# Interfaces.net
KiCad netlist of a schematic drawn in Altium Designer
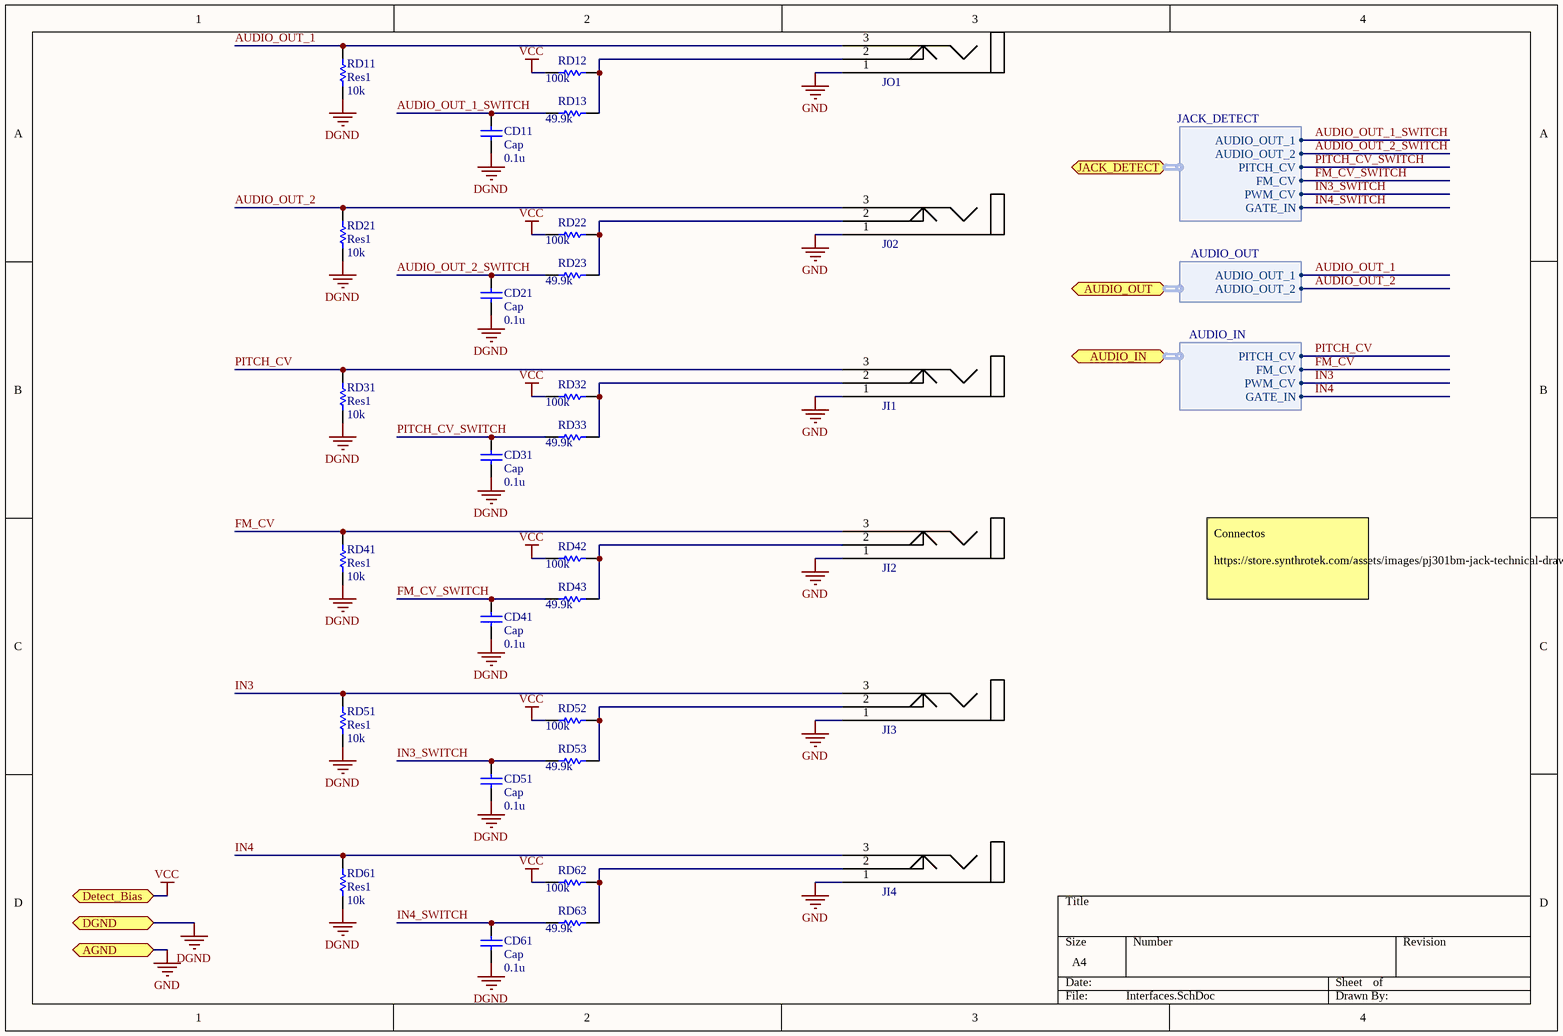
[diagram p0: Interfaces.SchDoc]

(export (version "E")
  (design (tool "Eeschema 10.0.6"))
  (components
    (comp (ref "CD11")
      (value "Cap")
      (footprint "C 0603 / 1608")
      (description "Capacitor")
      (fields (field (name "ALTIUM_VALUE") "0.1u") (field (name "PUBLISHER") "Altium Limited"))
      (libsource (lib "Standard") (part "Cap"))
    )
    (comp (ref "CD21")
      (value "Cap")
      (footprint "C 0603 / 1608")
      (description "Capacitor")
      (fields (field (name "ALTIUM_VALUE") "0.1u") (field (name "PUBLISHER") "Altium Limited"))
      (libsource (lib "Standard") (part "Cap"))
    )
    (comp (ref "CD31")
      (value "Cap")
      (footprint "C 0603 / 1608")
      (description "Capacitor")
      (fields (field (name "ALTIUM_VALUE") "0.1u") (field (name "PUBLISHER") "Altium Limited"))
      (libsource (lib "Standard") (part "Cap"))
    )
    (comp (ref "CD41")
      (value "Cap")
      (footprint "C 0603 / 1608")
      (description "Capacitor")
      (fields (field (name "ALTIUM_VALUE") "0.1u") (field (name "PUBLISHER") "Altium Limited"))
      (libsource (lib "Standard") (part "Cap"))
    )
    (comp (ref "CD51")
      (value "Cap")
      (footprint "C 0603 / 1608")
      (description "Capacitor")
      (fields (field (name "ALTIUM_VALUE") "0.1u") (field (name "PUBLISHER") "Altium Limited"))
      (libsource (lib "Standard") (part "Cap"))
    )
    (comp (ref "CD61")
      (value "Cap")
      (footprint "C 0603 / 1608")
      (description "Capacitor")
      (fields (field (name "ALTIUM_VALUE") "0.1u") (field (name "PUBLISHER") "Altium Limited"))
      (libsource (lib "Standard") (part "Cap"))
    )
    (comp (ref "J02") (value "PJ-301") (footprint "PJ-301") (libsource (lib "Connectors") (part "PJ-301")))
    (comp (ref "JI1") (value "PJ-301") (footprint "PJ-301") (libsource (lib "Connectors") (part "PJ-301")))
    (comp (ref "JI2") (value "PJ-301") (footprint "PJ-301") (libsource (lib "Connectors") (part "PJ-301")))
    (comp (ref "JI3") (value "PJ-301") (footprint "PJ-301") (libsource (lib "Connectors") (part "PJ-301")))
    (comp (ref "JI4") (value "PJ-301") (footprint "PJ-301") (libsource (lib "Connectors") (part "PJ-301")))
    (comp (ref "JO1") (value "PJ-301") (footprint "PJ-301") (libsource (lib "Connectors") (part "PJ-301")))
    (comp (ref "RD11")
      (value "Res1")
      (footprint "RES0603R")
      (description "Resistor")
      (fields (field (name "ALTIUM_VALUE") "10k") (field (name "PUBLISHER") "Altium Limited"))
      (libsource (lib "Standard") (part "Res1"))
    )
    (comp (ref "RD12")
      (value "100k")
      (footprint "RES0603R")
      (description "Resistor")
      (fields (field (name "Comment") "Res1") (field (name "PUBLISHER") "Altium Limited"))
      (libsource (lib "Standard") (part "Res1"))
    )
    (comp (ref "RD13")
      (value "49.9k")
      (footprint "RES0603R")
      (description "Resistor")
      (fields (field (name "Comment") "Res1") (field (name "PUBLISHER") "Altium Limited"))
      (libsource (lib "Standard") (part "Res1"))
    )
    (comp (ref "RD21")
      (value "Res1")
      (footprint "RES0603R")
      (description "Resistor")
      (fields (field (name "ALTIUM_VALUE") "10k") (field (name "PUBLISHER") "Altium Limited"))
      (libsource (lib "Standard") (part "Res1"))
    )
    (comp (ref "RD22")
      (value "100k")
      (footprint "RES0603R")
      (description "Resistor")
      (fields (field (name "Comment") "Res1") (field (name "PUBLISHER") "Altium Limited"))
      (libsource (lib "Standard") (part "Res1"))
    )
    (comp (ref "RD23")
      (value "49.9k")
      (footprint "RES0603R")
      (description "Resistor")
      (fields (field (name "Comment") "Res1") (field (name "PUBLISHER") "Altium Limited"))
      (libsource (lib "Standard") (part "Res1"))
    )
    (comp (ref "RD31")
      (value "Res1")
      (footprint "RES0603R")
      (description "Resistor")
      (fields (field (name "ALTIUM_VALUE") "10k") (field (name "PUBLISHER") "Altium Limited"))
      (libsource (lib "Standard") (part "Res1"))
    )
    (comp (ref "RD32")
      (value "100k")
      (footprint "RES0603R")
      (description "Resistor")
      (fields (field (name "Comment") "Res1") (field (name "PUBLISHER") "Altium Limited"))
      (libsource (lib "Standard") (part "Res1"))
    )
    (comp (ref "RD33")
      (value "49.9k")
      (footprint "RES0603R")
      (description "Resistor")
      (fields (field (name "Comment") "Res1") (field (name "PUBLISHER") "Altium Limited"))
      (libsource (lib "Standard") (part "Res1"))
    )
    (comp (ref "RD41")
      (value "Res1")
      (footprint "RES0603R")
      (description "Resistor")
      (fields (field (name "ALTIUM_VALUE") "10k") (field (name "PUBLISHER") "Altium Limited"))
      (libsource (lib "Standard") (part "Res1"))
    )
    (comp (ref "RD42")
      (value "100k")
      (footprint "RES0603R")
      (description "Resistor")
      (fields (field (name "Comment") "Res1") (field (name "PUBLISHER") "Altium Limited"))
      (libsource (lib "Standard") (part "Res1"))
    )
    (comp (ref "RD43")
      (value "49.9k")
      (footprint "RES0603R")
      (description "Resistor")
      (fields (field (name "Comment") "Res1") (field (name "PUBLISHER") "Altium Limited"))
      (libsource (lib "Standard") (part "Res1"))
    )
    (comp (ref "RD51")
      (value "Res1")
      (footprint "RES0603R")
      (description "Resistor")
      (fields (field (name "ALTIUM_VALUE") "10k") (field (name "PUBLISHER") "Altium Limited"))
      (libsource (lib "Standard") (part "Res1"))
    )
    (comp (ref "RD52")
      (value "100k")
      (footprint "RES0603R")
      (description "Resistor")
      (fields (field (name "Comment") "Res1") (field (name "PUBLISHER") "Altium Limited"))
      (libsource (lib "Standard") (part "Res1"))
    )
    (comp (ref "RD53")
      (value "49.9k")
      (footprint "RES0603R")
      (description "Resistor")
      (fields (field (name "Comment") "Res1") (field (name "PUBLISHER") "Altium Limited"))
      (libsource (lib "Standard") (part "Res1"))
    )
    (comp (ref "RD61")
      (value "Res1")
      (footprint "RES0603R")
      (description "Resistor")
      (fields (field (name "ALTIUM_VALUE") "10k") (field (name "PUBLISHER") "Altium Limited"))
      (libsource (lib "Standard") (part "Res1"))
    )
    (comp (ref "RD62")
      (value "100k")
      (footprint "RES0603R")
      (description "Resistor")
      (fields (field (name "Comment") "Res1") (field (name "PUBLISHER") "Altium Limited"))
      (libsource (lib "Standard") (part "Res1"))
    )
    (comp (ref "RD63")
      (value "49.9k")
      (footprint "RES0603R")
      (description "Resistor")
      (fields (field (name "Comment") "Res1") (field (name "PUBLISHER") "Altium Limited"))
      (libsource (lib "Standard") (part "Res1"))
    )
  )
  (nets
    (net (code "4") (name "/AUDIO_OUT_1") (class "Default")
      (node (ref "JO1") (pin "3") (pinfunction "Ring_3") (pintype "passive"))
      (node (ref "RD11") (pin "2") (pinfunction "2_2") (pintype "passive"))
    )
    (net (code "5") (name "/AUDIO_OUT_1_SWITCH") (class "Default")
      (node (ref "CD11") (pin "2") (pinfunction "2_2") (pintype "passive"))
      (node (ref "RD13") (pin "2") (pinfunction "2_2") (pintype "passive"))
    )
    (net (code "6") (name "/AUDIO_OUT_2") (class "Default")
      (node (ref "J02") (pin "3") (pinfunction "Ring_3") (pintype "passive"))
      (node (ref "RD21") (pin "2") (pinfunction "2_2") (pintype "passive"))
    )
    (net (code "7") (name "/AUDIO_OUT_2_SWITCH") (class "Default")
      (node (ref "CD21") (pin "2") (pinfunction "2_2") (pintype "passive"))
      (node (ref "RD23") (pin "2") (pinfunction "2_2") (pintype "passive"))
    )
    (net (code "8") (name "/FM_CV") (class "Default")
      (node (ref "JI2") (pin "3") (pinfunction "Ring_3") (pintype "passive"))
      (node (ref "RD41") (pin "2") (pinfunction "2_2") (pintype "passive"))
    )
    (net (code "9") (name "/FM_CV_SWITCH") (class "Default")
      (node (ref "CD41") (pin "2") (pinfunction "2_2") (pintype "passive"))
      (node (ref "RD43") (pin "2") (pinfunction "2_2") (pintype "passive"))
    )
    (net (code "10") (name "/IN3") (class "Default")
      (node (ref "JI3") (pin "3") (pinfunction "Ring_3") (pintype "passive"))
      (node (ref "RD51") (pin "2") (pinfunction "2_2") (pintype "passive"))
    )
    (net (code "11") (name "/IN3_SWITCH") (class "Default")
      (node (ref "CD51") (pin "2") (pinfunction "2_2") (pintype "passive"))
      (node (ref "RD53") (pin "2") (pinfunction "2_2") (pintype "passive"))
    )
    (net (code "12") (name "/IN4") (class "Default")
      (node (ref "JI4") (pin "3") (pinfunction "Ring_3") (pintype "passive"))
      (node (ref "RD61") (pin "2") (pinfunction "2_2") (pintype "passive"))
    )
    (net (code "13") (name "/IN4_SWITCH") (class "Default")
      (node (ref "CD61") (pin "2") (pinfunction "2_2") (pintype "passive"))
      (node (ref "RD63") (pin "2") (pinfunction "2_2") (pintype "passive"))
    )
    (net (code "14") (name "/PITCH_CV") (class "Default")
      (node (ref "JI1") (pin "3") (pinfunction "Ring_3") (pintype "passive"))
      (node (ref "RD31") (pin "2") (pinfunction "2_2") (pintype "passive"))
    )
    (net (code "15") (name "/PITCH_CV_SWITCH") (class "Default")
      (node (ref "CD31") (pin "2") (pinfunction "2_2") (pintype "passive"))
      (node (ref "RD33") (pin "2") (pinfunction "2_2") (pintype "passive"))
    )
    (net (code "19") (name "DGND") (class "Default")
      (node (ref "CD11") (pin "1") (pinfunction "1_1") (pintype "passive"))
      (node (ref "CD21") (pin "1") (pinfunction "1_1") (pintype "passive"))
      (node (ref "CD31") (pin "1") (pinfunction "1_1") (pintype "passive"))
      (node (ref "CD41") (pin "1") (pinfunction "1_1") (pintype "passive"))
      (node (ref "CD51") (pin "1") (pinfunction "1_1") (pintype "passive"))
      (node (ref "CD61") (pin "1") (pinfunction "1_1") (pintype "passive"))
      (node (ref "RD11") (pin "1") (pinfunction "1_1") (pintype "passive"))
      (node (ref "RD21") (pin "1") (pinfunction "1_1") (pintype "passive"))
      (node (ref "RD31") (pin "1") (pinfunction "1_1") (pintype "passive"))
      (node (ref "RD41") (pin "1") (pinfunction "1_1") (pintype "passive"))
      (node (ref "RD51") (pin "1") (pinfunction "1_1") (pintype "passive"))
      (node (ref "RD61") (pin "1") (pinfunction "1_1") (pintype "passive"))
    )
    (net (code "20") (name "GND") (class "Default")
      (node (ref "J02") (pin "1") (pinfunction "Sleeve_1") (pintype "passive"))
      (node (ref "JI1") (pin "1") (pinfunction "Sleeve_1") (pintype "passive"))
      (node (ref "JI2") (pin "1") (pinfunction "Sleeve_1") (pintype "passive"))
      (node (ref "JI3") (pin "1") (pinfunction "Sleeve_1") (pintype "passive"))
      (node (ref "JI4") (pin "1") (pinfunction "Sleeve_1") (pintype "passive"))
      (node (ref "JO1") (pin "1") (pinfunction "Sleeve_1") (pintype "passive"))
    )
    (net (code "21") (name "Net-(J02-Tip)") (class "Default")
      (node (ref "J02") (pin "2") (pinfunction "Tip_2") (pintype "passive"))
      (node (ref "RD22") (pin "1") (pinfunction "1_1") (pintype "passive"))
      (node (ref "RD23") (pin "1") (pinfunction "1_1") (pintype "passive"))
    )
    (net (code "22") (name "Net-(JI1-Tip)") (class "Default")
      (node (ref "JI1") (pin "2") (pinfunction "Tip_2") (pintype "passive"))
      (node (ref "RD32") (pin "1") (pinfunction "1_1") (pintype "passive"))
      (node (ref "RD33") (pin "1") (pinfunction "1_1") (pintype "passive"))
    )
    (net (code "23") (name "Net-(JI2-Tip)") (class "Default")
      (node (ref "JI2") (pin "2") (pinfunction "Tip_2") (pintype "passive"))
      (node (ref "RD42") (pin "1") (pinfunction "1_1") (pintype "passive"))
      (node (ref "RD43") (pin "1") (pinfunction "1_1") (pintype "passive"))
    )
    (net (code "24") (name "Net-(JI3-Tip)") (class "Default")
      (node (ref "JI3") (pin "2") (pinfunction "Tip_2") (pintype "passive"))
      (node (ref "RD52") (pin "1") (pinfunction "1_1") (pintype "passive"))
      (node (ref "RD53") (pin "1") (pinfunction "1_1") (pintype "passive"))
    )
    (net (code "25") (name "Net-(JI4-Tip)") (class "Default")
      (node (ref "JI4") (pin "2") (pinfunction "Tip_2") (pintype "passive"))
      (node (ref "RD62") (pin "1") (pinfunction "1_1") (pintype "passive"))
      (node (ref "RD63") (pin "1") (pinfunction "1_1") (pintype "passive"))
    )
    (net (code "26") (name "Net-(JO1-Tip)") (class "Default")
      (node (ref "JO1") (pin "2") (pinfunction "Tip_2") (pintype "passive"))
      (node (ref "RD12") (pin "1") (pinfunction "1_1") (pintype "passive"))
      (node (ref "RD13") (pin "1") (pinfunction "1_1") (pintype "passive"))
    )
    (net (code "27") (name "VCC") (class "Default")
      (node (ref "RD12") (pin "2") (pinfunction "2_2") (pintype "passive"))
      (node (ref "RD22") (pin "2") (pinfunction "2_2") (pintype "passive"))
      (node (ref "RD32") (pin "2") (pinfunction "2_2") (pintype "passive"))
      (node (ref "RD42") (pin "2") (pinfunction "2_2") (pintype "passive"))
      (node (ref "RD52") (pin "2") (pinfunction "2_2") (pintype "passive"))
      (node (ref "RD62") (pin "2") (pinfunction "2_2") (pintype "passive"))
    )
  )
)
